# Thermistor.net
KiCad netlist of a schematic drawn in Altium Designer
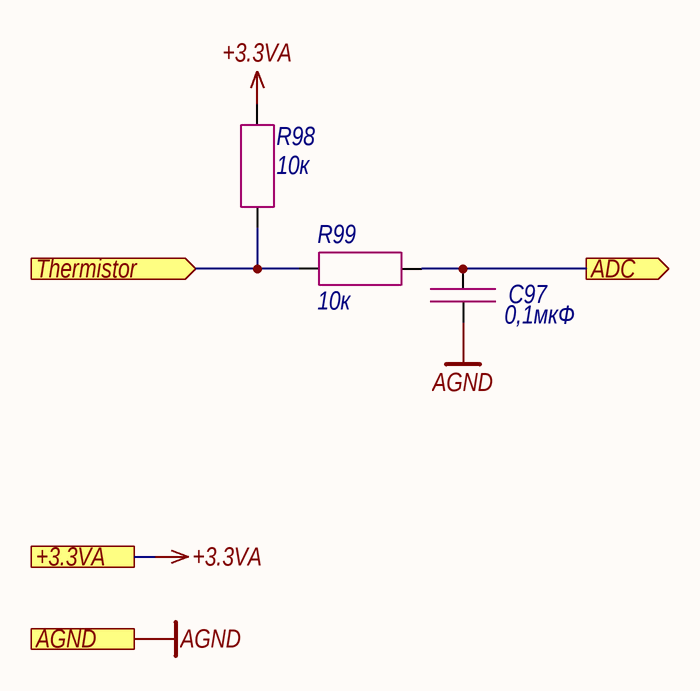
[diagram p0: Thermistor.SchDoc]

(export (version "E")
  (design (tool "Eeschema 10.0.6"))
  (components
    (comp (ref "C97")
      (value "0,1мкФ")
      (footprint "Pcb_library:CAP_0603")
      (fields (field (name "MANUFACTURER") "Murata"))
      (libsource (lib "Schem_library") (part "Capacitor"))
    )
    (comp (ref "R98")
      (value "10к")
      (footprint "Pcb_library:RES_0603")
      (fields (field (name "MANUFACTURER") "Yageo"))
      (libsource (lib "Schem_library") (part "Resistor"))
    )
    (comp (ref "R99")
      (value "10к")
      (footprint "Pcb_library:RES_0603")
      (fields (field (name "MANUFACTURER") "Yageo"))
      (libsource (lib "Schem_library") (part "Resistor"))
    )
  )
  (nets
    (net (code "1") (name "+3.3VA") (class "Default")
      (node (ref "R98") (pin "1") (pinfunction "1_1") (pintype "passive"))
    )
    (net (code "2") (name "/ADC") (class "Default")
      (node (ref "C97") (pin "1") (pinfunction "1_1") (pintype "passive"))
      (node (ref "R99") (pin "2") (pinfunction "2_2") (pintype "passive"))
    )
    (net (code "3") (name "/Thermistor") (class "Default")
      (node (ref "R98") (pin "2") (pinfunction "2_2") (pintype "passive"))
      (node (ref "R99") (pin "1") (pinfunction "1_1") (pintype "passive"))
    )
    (net (code "4") (name "AGND") (class "Default")
      (node (ref "C97") (pin "2") (pinfunction "2_2") (pintype "passive"))
    )
  )
)
